# Power_Supply.net
KiCad netlist of a schematic drawn in Altium Designer
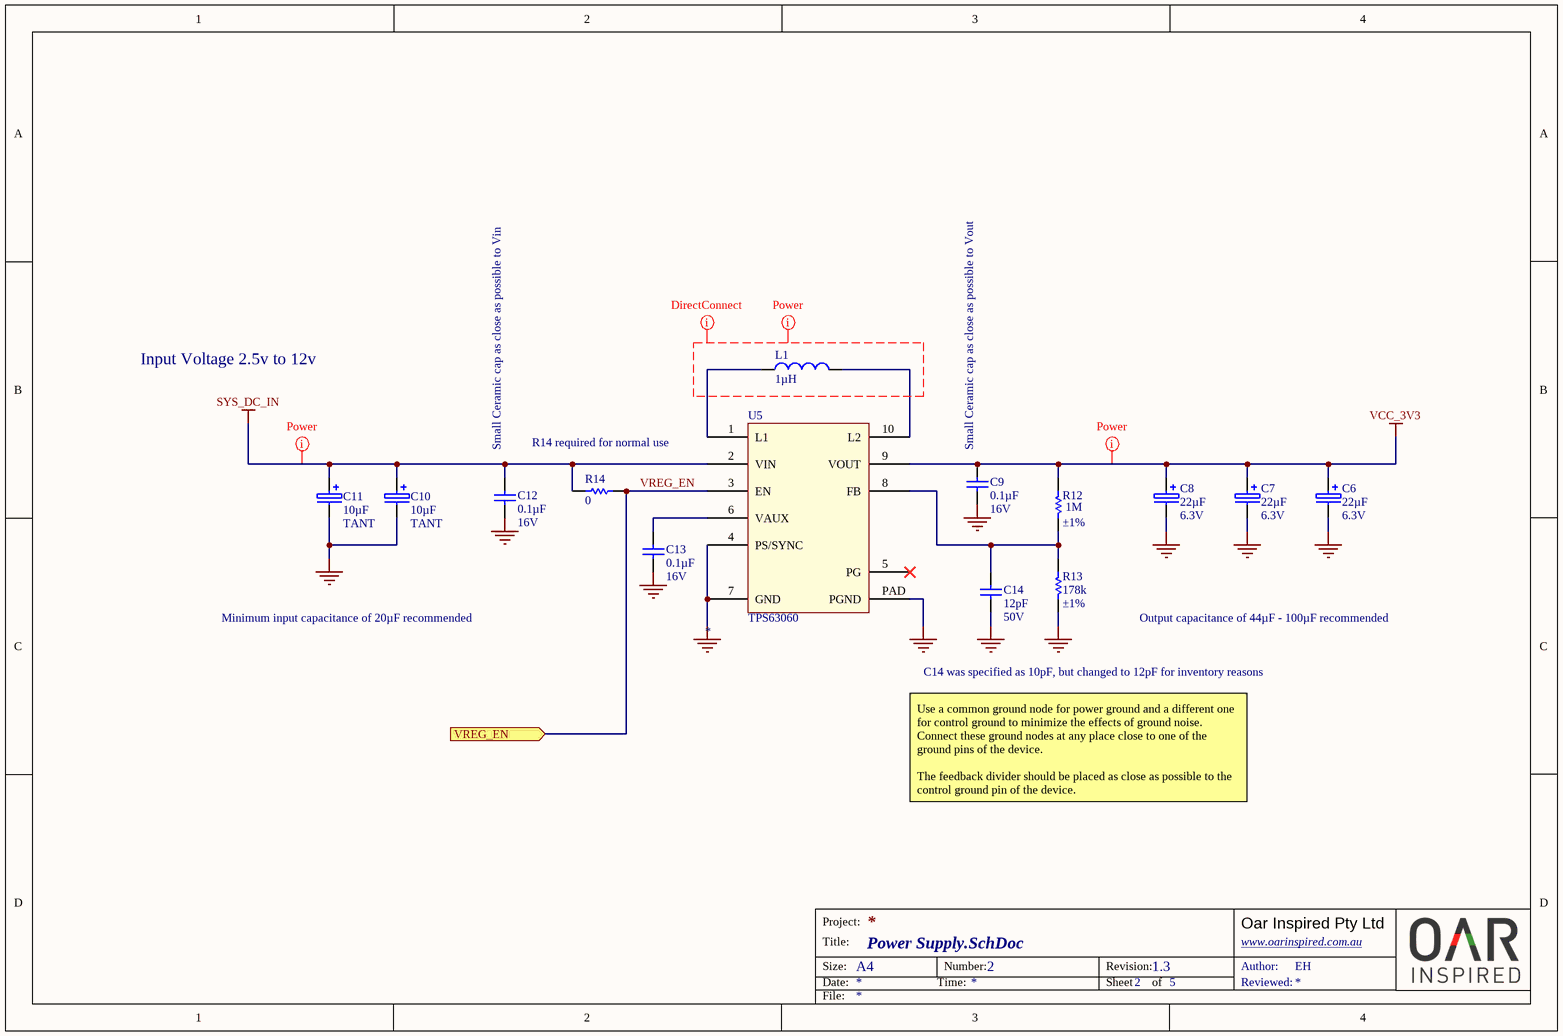
[diagram p0: Power Supply.SchDoc]

(export (version "E")
  (design (tool "Eeschema 10.0.6"))
  (components
    (comp (ref "C6")
      (value "22µF")
      (footprint "CASE-A")
      (description "CAP TANT 22UF 6.3V 10% 1206")
      (fields
        (field (name "PART NUMBER") "C01754")
        (field (name "VOLTAGE") "6.3V")
        (field (name "MANUFACTURER") "AVX Corporation")
      )
      (libsource (lib "Azure Components") (part "ELECTRO"))
    )
    (comp (ref "C7")
      (value "22µF")
      (footprint "CASE-A")
      (description "CAP TANT 22UF 6.3V 10% 1206")
      (fields
        (field (name "PART NUMBER") "C01754")
        (field (name "VOLTAGE") "6.3V")
        (field (name "MANUFACTURER") "AVX Corporation")
      )
      (libsource (lib "Azure Components") (part "ELECTRO"))
    )
    (comp (ref "C8")
      (value "22µF")
      (footprint "CASE-A")
      (description "CAP TANT 22UF 6.3V 10% 1206")
      (fields
        (field (name "PART NUMBER") "C01754")
        (field (name "VOLTAGE") "6.3V")
        (field (name "MANUFACTURER") "AVX Corporation")
      )
      (libsource (lib "Azure Components") (part "ELECTRO"))
    )
    (comp (ref "C9")
      (value "0.1µF")
      (footprint "C0402")
      (description "CAP CER 0.1UF 16V X7R 0402")
      (fields
        (field (name "VOLTAGE") "16V")
        (field (name "PART NUMBER") "C01054")
        (field (name "MANUFACTURER") "MuRata")
      )
      (libsource (lib "Azure Components") (part "CAP"))
    )
    (comp (ref "C10")
      (value "10µF")
      (footprint "CASE-A")
      (description "CAP TANT 10UF 16V 20% 1206")
      (fields
        (field (name "PART NUMBER") "C01756")
        (field (name "VOLTAGE") "16V")
        (field (name "TYPE") "TANT")
      )
      (libsource (lib "Azure Components") (part "ELECTRO"))
    )
    (comp (ref "C11")
      (value "10µF")
      (footprint "CASE-A")
      (description "CAP TANT 10UF 16V 20% 1206")
      (fields
        (field (name "PART NUMBER") "C01756")
        (field (name "VOLTAGE") "16V")
        (field (name "TYPE") "TANT")
      )
      (libsource (lib "Azure Components") (part "ELECTRO"))
    )
    (comp (ref "C12")
      (value "0.1µF")
      (footprint "C0402")
      (description "CAP CER 0.1UF 16V X7R 0402")
      (fields
        (field (name "VOLTAGE") "16V")
        (field (name "PART NUMBER") "C01054")
        (field (name "MANUFACTURER") "MuRata")
      )
      (libsource (lib "Azure Components") (part "CAP"))
    )
    (comp (ref "C13")
      (value "0.1µF")
      (footprint "C0402")
      (description "CAP CER 0.1UF 16V X7R 0402")
      (fields
        (field (name "VOLTAGE") "16V")
        (field (name "PART NUMBER") "C01054")
        (field (name "MANUFACTURER") "MuRata")
      )
      (libsource (lib "Azure Components") (part "CAP"))
    )
    (comp (ref "C14")
      (value "12pF")
      (footprint "C0402")
      (description "CAP CER 12PF 50V NP0 0402")
      (fields
        (field (name "VOLTAGE") "50V")
        (field (name "PART NUMBER") "C00087")
        (field (name "MANUFACTURER") "MuRata")
      )
      (libsource (lib "Azure Components") (part "CAP"))
    )
    (comp (ref "L1")
      (value "1µH")
      (footprint "ASPI-4020S")
      (description "FIXED IND 1UH 2.15A 29 MOHM SMD")
      (fields (field (name "MANUFACTURER") "Abracon LLC") (field (name "PART NUMBER") "IND0044"))
      (libsource (lib "Azure Components") (part "IND"))
    )
    (comp (ref "R12")
      (value "1M")
      (footprint "R0603")
      (description "RES SMD 1M OHM 1% 1/10W 0603")
      (fields
        (field (name "TOLERANCE") "±1%")
        (field (name "POWER") "0.1W, 1/10W")
        (field (name "PART NUMBER") "RES_YAG_RC0603FR-071ML")
      )
      (libsource (lib "Azure Components") (part "RES"))
    )
    (comp (ref "R13")
      (value "178k")
      (footprint "R0603")
      (description "RES SMD 178K OHM 1% 1/10W 0603")
      (fields
        (field (name "TOLERANCE") "±1%")
        (field (name "POWER") "0.1W, 1/10W")
        (field (name "PART NUMBER") "RES_YAG_RC0603FR-07178KL")
      )
      (libsource (lib "Azure Components") (part "RES"))
    )
    (comp (ref "R14")
      (value "0")
      (footprint "R0402")
      (description "RES SMD 0.0OHM JUMPER 1/16W 0402")
      (fields (field (name "PART NUMBER") "RES_YAG_RC0402JR-070RL") (field (name "MANUFACTURER") "Yageo"))
      (libsource (lib "Azure Components") (part "RES"))
    )
    (comp (ref "U5")
      (value "TPS63060")
      (footprint "PWSON-N10")
      (description "IC REG BUCK BOOST ADJ 2A 10WSON")
      (fields
        (field (name "MANUFACTURER") "Texas Instruments")
        (field (name "PART NUMBER") "5030")
        (field (name "SMALLFOOTPRINT") "*")
      )
      (libsource (lib "Azure Components") (part "TSP63060"))
    )
  )
  (nets
    (net (code "1") (name "/VREG_EN") (class "Default")
      (node (ref "R14") (pin "2") (pinfunction "2_2") (pintype "passive"))
      (node (ref "U5") (pin "3") (pinfunction "EN_3") (pintype "passive"))
    )
    (net (code "2") (name "GND") (class "Default")
      (node (ref "C10") (pin "2") (pintype "passive"))
      (node (ref "C11") (pin "2") (pintype "passive"))
      (node (ref "C12") (pin "2") (pinfunction "2_2") (pintype "passive"))
      (node (ref "C13") (pin "2") (pinfunction "2_2") (pintype "passive"))
      (node (ref "C14") (pin "2") (pinfunction "2_2") (pintype "passive"))
      (node (ref "C6") (pin "2") (pintype "passive"))
      (node (ref "C7") (pin "2") (pintype "passive"))
      (node (ref "C8") (pin "2") (pintype "passive"))
      (node (ref "C9") (pin "2") (pinfunction "2_2") (pintype "passive"))
      (node (ref "R13") (pin "2") (pinfunction "2_2") (pintype "passive"))
      (node (ref "U5") (pin "4") (pinfunction "PS/SYNC_4") (pintype "passive"))
      (node (ref "U5") (pin "7") (pinfunction "GND_7") (pintype "power_in"))
      (node (ref "U5") (pin "PAD") (pinfunction "PGND_PAD") (pintype "power_in"))
    )
    (net (code "3") (name "Net-(U5-FB)") (class "Default")
      (node (ref "C14") (pin "1") (pinfunction "1_1") (pintype "passive"))
      (node (ref "R12") (pin "2") (pinfunction "2_2") (pintype "passive"))
      (node (ref "R13") (pin "1") (pinfunction "1_1") (pintype "passive"))
      (node (ref "U5") (pin "8") (pinfunction "FB_8") (pintype "passive"))
    )
    (net (code "4") (name "Net-(U5-L1)") (class "Default")
      (node (ref "L1") (pin "1") (pinfunction "1_1") (pintype "passive"))
      (node (ref "U5") (pin "1") (pinfunction "L1_1") (pintype "passive"))
    )
    (net (code "5") (name "Net-(U5-L2)") (class "Default")
      (node (ref "L1") (pin "2") (pinfunction "2_2") (pintype "passive"))
      (node (ref "U5") (pin "10") (pinfunction "L2_10") (pintype "power_in"))
    )
    (net (code "6") (name "Net-(U5-VAUX)") (class "Default")
      (node (ref "C13") (pin "1") (pinfunction "1_1") (pintype "passive"))
      (node (ref "U5") (pin "6") (pinfunction "VAUX_6") (pintype "passive"))
    )
    (net (code "7") (name "SYS_DC_IN") (class "Default")
      (node (ref "C10") (pin "1") (pintype "passive"))
      (node (ref "C11") (pin "1") (pintype "passive"))
      (node (ref "C12") (pin "1") (pinfunction "1_1") (pintype "passive"))
      (node (ref "R14") (pin "1") (pinfunction "1_1") (pintype "passive"))
      (node (ref "U5") (pin "2") (pinfunction "VIN_2") (pintype "passive"))
    )
    (net (code "8") (name "VCC_3V3") (class "Default")
      (node (ref "C6") (pin "1") (pintype "passive"))
      (node (ref "C7") (pin "1") (pintype "passive"))
      (node (ref "C8") (pin "1") (pintype "passive"))
      (node (ref "C9") (pin "1") (pinfunction "1_1") (pintype "passive"))
      (node (ref "R12") (pin "1") (pinfunction "1_1") (pintype "passive"))
      (node (ref "U5") (pin "9") (pinfunction "VOUT_9") (pintype "power_in"))
    )
    (net (code "9") (name "unconnected-(U5-PG-Pad5)") (class "Default")
      (node (ref "U5") (pin "5") (pinfunction "PG_5") (pintype "power_in+no_connect"))
    )
  )
)
